# mkstepper17.net
KiCad netlist of a schematic drawn in EAGLE
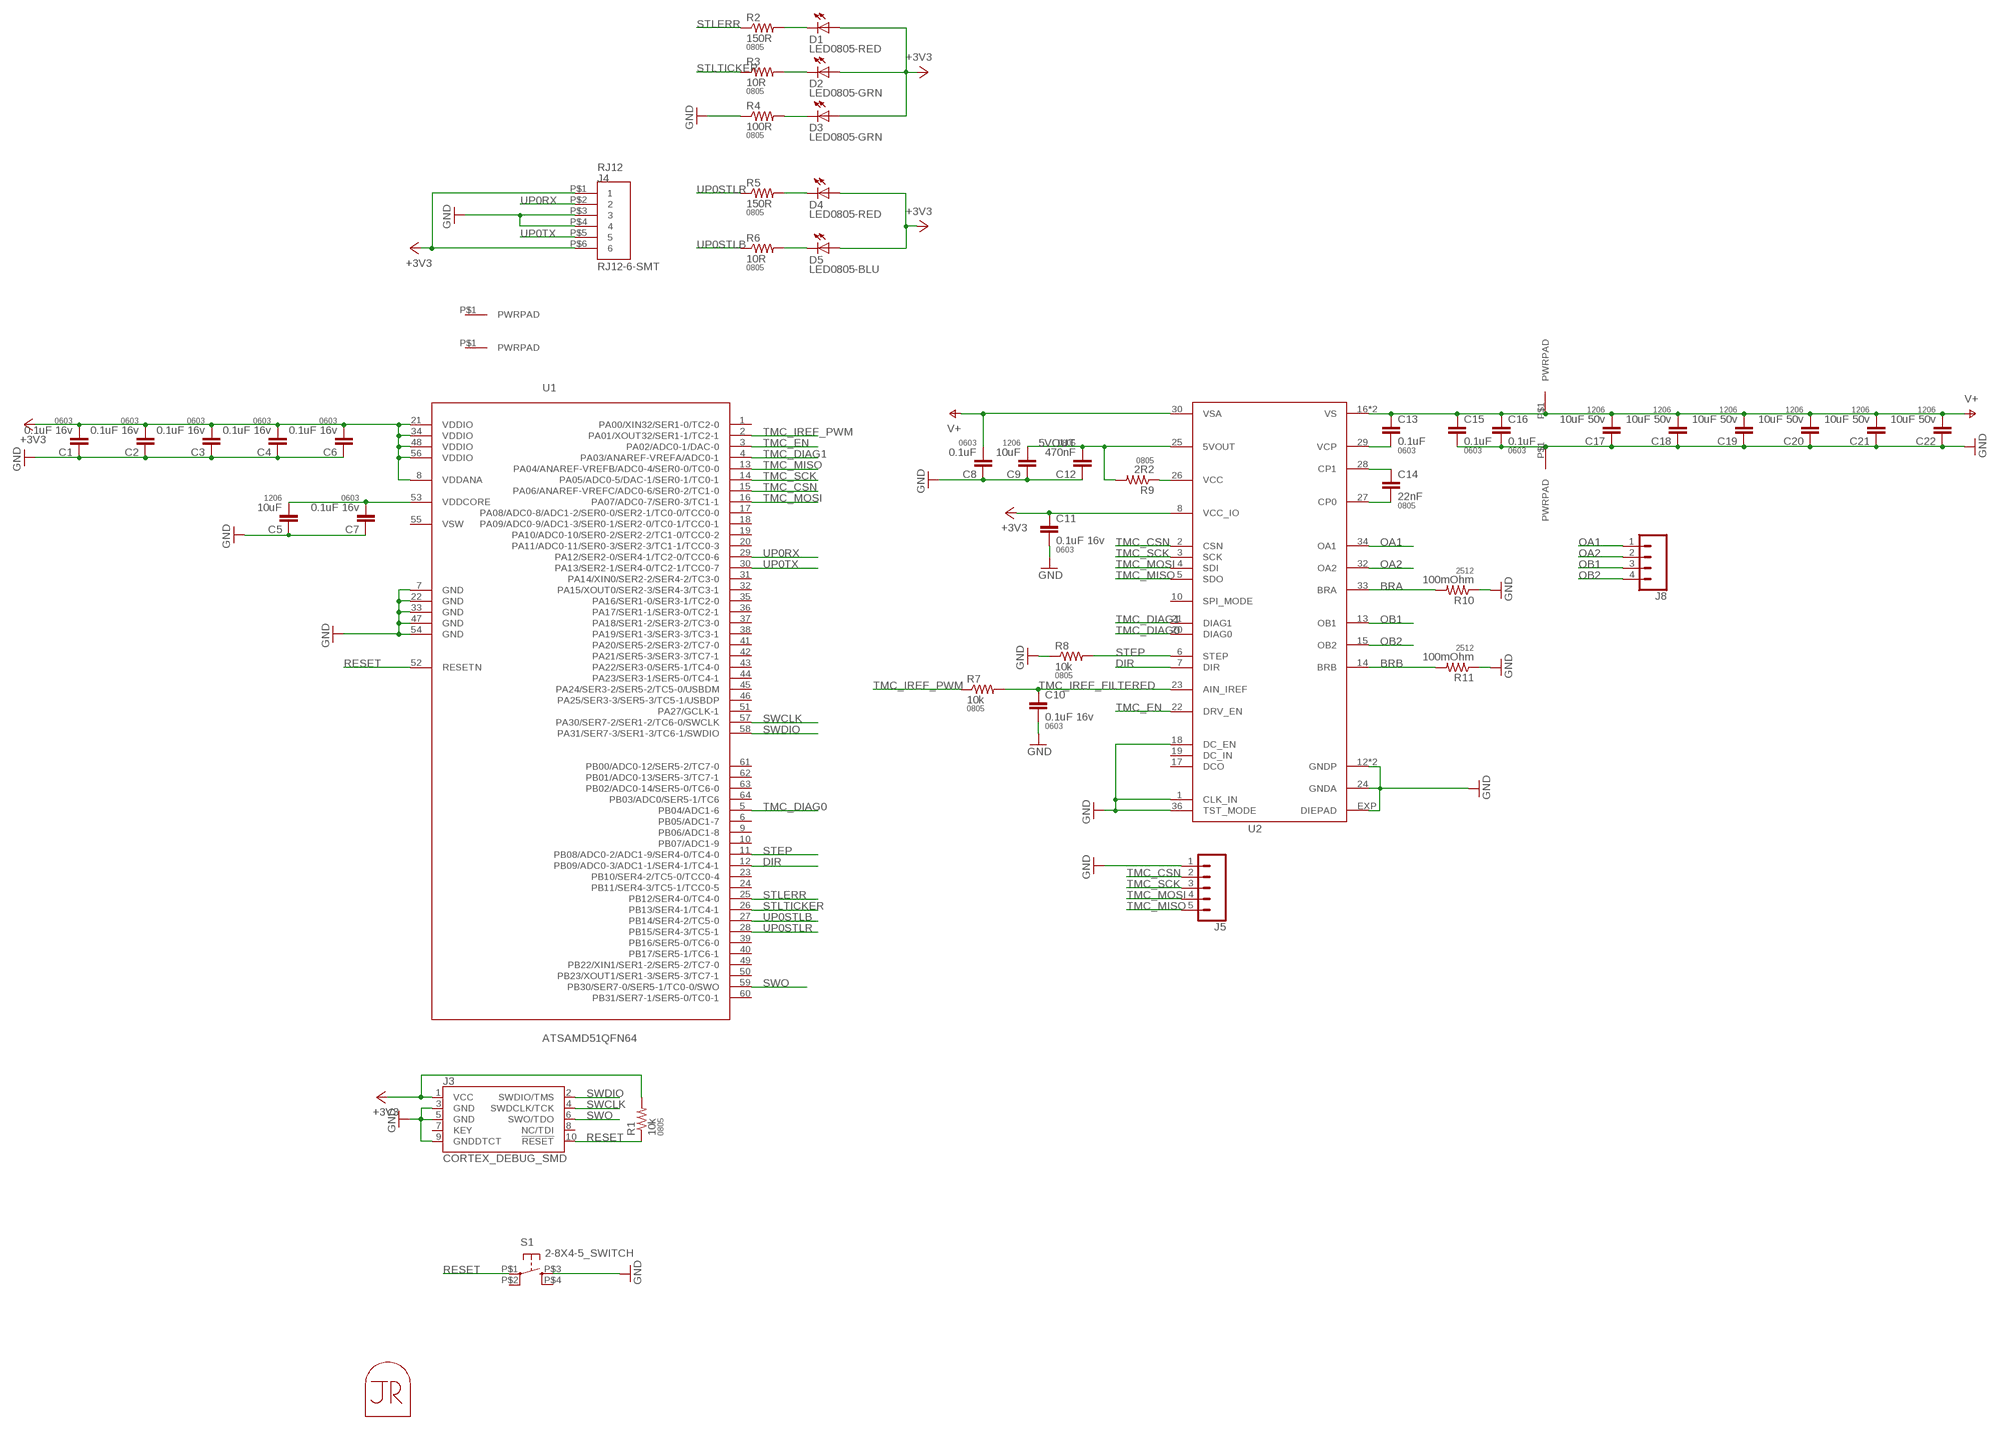
[diagram p0: schematic, sheet 1]

(export (version "E")
  (design (tool "Eeschema 10.0.6"))
  (components
    (comp (ref "C1")
      (value "0.1uF 16v")
      (footprint "eagle-import:0603-CAP")
      (libsource (lib "eagle-import") (part "CAP0603-CAP"))
    )
    (comp (ref "C2")
      (value "0.1uF 16v")
      (footprint "eagle-import:0603-CAP")
      (libsource (lib "eagle-import") (part "CAP0603-CAP"))
    )
    (comp (ref "C3")
      (value "0.1uF 16v")
      (footprint "eagle-import:0603-CAP")
      (libsource (lib "eagle-import") (part "CAP0603-CAP"))
    )
    (comp (ref "C4")
      (value "0.1uF 16v")
      (footprint "eagle-import:0603-CAP")
      (libsource (lib "eagle-import") (part "CAP0603-CAP"))
    )
    (comp (ref "C5")
      (value "10uF")
      (footprint "eagle-import:1206")
      (libsource (lib "eagle-import") (part "CAP1206"))
    )
    (comp (ref "C6")
      (value "0.1uF 16v")
      (footprint "eagle-import:0603-CAP")
      (libsource (lib "eagle-import") (part "CAP0603-CAP"))
    )
    (comp (ref "C7")
      (value "0.1uF 16v")
      (footprint "eagle-import:0603-CAP")
      (libsource (lib "eagle-import") (part "CAP0603-CAP"))
    )
    (comp (ref "C8")
      (value "0.1uF")
      (footprint "eagle-import:0603-CAP")
      (libsource (lib "eagle-import") (part "CAP0603-CAP"))
    )
    (comp (ref "C9")
      (value "10uF")
      (footprint "eagle-import:1206")
      (libsource (lib "eagle-import") (part "CAP1206"))
    )
    (comp (ref "C10")
      (value "0.1uF 16v")
      (footprint "eagle-import:0603-CAP")
      (libsource (lib "eagle-import") (part "CAP0603-CAP"))
    )
    (comp (ref "C11")
      (value "0.1uF 16v")
      (footprint "eagle-import:0603-CAP")
      (libsource (lib "eagle-import") (part "CAP0603-CAP"))
    )
    (comp (ref "C12")
      (value "470nF")
      (footprint "eagle-import:0805")
      (libsource (lib "eagle-import") (part "CAP0805"))
    )
    (comp (ref "C13")
      (value "0.1uF")
      (footprint "eagle-import:0603-CAP")
      (libsource (lib "eagle-import") (part "CAP0603-CAP"))
    )
    (comp (ref "C14")
      (value "22nF")
      (footprint "eagle-import:0805")
      (libsource (lib "eagle-import") (part "CAP0805"))
    )
    (comp (ref "C15")
      (value "0.1uF")
      (footprint "eagle-import:0603-CAP")
      (libsource (lib "eagle-import") (part "CAP0603-CAP"))
    )
    (comp (ref "C16")
      (value "0.1uF")
      (footprint "eagle-import:0603-CAP")
      (libsource (lib "eagle-import") (part "CAP0603-CAP"))
    )
    (comp (ref "C17")
      (value "10uF 50v")
      (footprint "eagle-import:1206")
      (libsource (lib "eagle-import") (part "CAP1206"))
    )
    (comp (ref "C18")
      (value "10uF 50v")
      (footprint "eagle-import:1206")
      (libsource (lib "eagle-import") (part "CAP1206"))
    )
    (comp (ref "C19")
      (value "10uF 50v")
      (footprint "eagle-import:1206")
      (libsource (lib "eagle-import") (part "CAP1206"))
    )
    (comp (ref "C20")
      (value "10uF 50v")
      (footprint "eagle-import:1206")
      (libsource (lib "eagle-import") (part "CAP1206"))
    )
    (comp (ref "C21")
      (value "10uF 50v")
      (footprint "eagle-import:1206")
      (libsource (lib "eagle-import") (part "CAP1206"))
    )
    (comp (ref "C22")
      (value "10uF 50v")
      (footprint "eagle-import:1206")
      (libsource (lib "eagle-import") (part "CAP1206"))
    )
    (comp (ref "D1")
      (value "LED0805-RED")
      (footprint "eagle-import:LED0805")
      (libsource (lib "eagle-import") (part "LED0805"))
    )
    (comp (ref "D2")
      (value "LED0805-GRN")
      (footprint "eagle-import:LED0805")
      (libsource (lib "eagle-import") (part "LED0805"))
    )
    (comp (ref "D3")
      (value "LED0805-GRN")
      (footprint "eagle-import:LED0805")
      (libsource (lib "eagle-import") (part "LED0805"))
    )
    (comp (ref "D4")
      (value "LED0805-RED")
      (footprint "eagle-import:LED0805")
      (libsource (lib "eagle-import") (part "LED0805"))
    )
    (comp (ref "D5")
      (value "LED0805-BLU")
      (footprint "eagle-import:LED0805")
      (libsource (lib "eagle-import") (part "LED0805"))
    )
    (comp (ref "J1")
      (value "PWRPADM3")
      (footprint "eagle-import:PWRPAD_3-25MM")
      (libsource (lib "eagle-import") (part "PWRPADM3"))
    )
    (comp (ref "J2")
      (value "PWRPADM3")
      (footprint "eagle-import:PWRPAD_3-25MM")
      (libsource (lib "eagle-import") (part "PWRPADM3"))
    )
    (comp (ref "J3")
      (value "CORTEX_DEBUG_SMD")
      (footprint "eagle-import:SAMTECH_FTSH-105-01")
      (libsource (lib "eagle-import") (part "CORTEX_DEBUG_SMD"))
    )
    (comp (ref "J4")
      (value "RJ12-6-SMT")
      (footprint "eagle-import:RJ12-6-SMT")
      (libsource (lib "eagle-import") (part "RJ12-6-SMT"))
    )
    (comp (ref "J5")
      (value "CONN_05NO_SILK")
      (footprint "eagle-import:1X05_NO_SILK")
      (libsource (lib "eagle-import") (part "CONN_05NO_SILK"))
    )
    (comp (ref "J6")
      (value "PWRPAD")
      (footprint "eagle-import:PWRPAD_M3-PEM-MOUNT")
      (libsource (lib "eagle-import") (part "PWRPAD"))
    )
    (comp (ref "J7")
      (value "PWRPAD")
      (footprint "eagle-import:PWRPAD_M3-PEM-MOUNT")
      (libsource (lib "eagle-import") (part "PWRPAD"))
    )
    (comp (ref "J8")
      (value "CONN_04LONGPADS")
      (footprint "eagle-import:1X04_LONGPADS")
      (libsource (lib "eagle-import") (part "CONN_04LONGPADS"))
    )
    (comp (ref "MP1")
      (value "JRTOMBSTONE")
      (footprint "eagle-import:JRTOMBSTONE")
      (libsource (lib "eagle-import") (part "JRTOMBSTONE"))
    )
    (comp (ref "R1")
      (value "10k")
      (footprint "eagle-import:0805")
      (libsource (lib "eagle-import") (part "RESISTOR0805-RES"))
    )
    (comp (ref "R2")
      (value "150R")
      (footprint "eagle-import:0805")
      (libsource (lib "eagle-import") (part "RESISTOR0805-RES"))
    )
    (comp (ref "R3")
      (value "10R")
      (footprint "eagle-import:0805")
      (libsource (lib "eagle-import") (part "RESISTOR0805-RES"))
    )
    (comp (ref "R4")
      (value "100R")
      (footprint "eagle-import:0805")
      (libsource (lib "eagle-import") (part "RESISTOR0805-RES"))
    )
    (comp (ref "R5")
      (value "150R")
      (footprint "eagle-import:0805")
      (libsource (lib "eagle-import") (part "RESISTOR0805-RES"))
    )
    (comp (ref "R6")
      (value "10R")
      (footprint "eagle-import:0805")
      (libsource (lib "eagle-import") (part "RESISTOR0805-RES"))
    )
    (comp (ref "R7")
      (value "10k")
      (footprint "eagle-import:0805")
      (libsource (lib "eagle-import") (part "RESISTOR0805-RES"))
    )
    (comp (ref "R8")
      (value "10k")
      (footprint "eagle-import:0805")
      (libsource (lib "eagle-import") (part "RESISTOR0805-RES"))
    )
    (comp (ref "R9")
      (value "2R2")
      (footprint "eagle-import:0805")
      (libsource (lib "eagle-import") (part "RESISTOR0805-RES"))
    )
    (comp (ref "R10")
      (value "100mOhm")
      (footprint "eagle-import:R2512")
      (libsource (lib "eagle-import") (part "RESISTOR2512"))
    )
    (comp (ref "R11")
      (value "100mOhm")
      (footprint "eagle-import:R2512")
      (libsource (lib "eagle-import") (part "RESISTOR2512"))
    )
    (comp (ref "S1")
      (value "2-8X4-5_SWITCH")
      (footprint "eagle-import:TACT-SWITCH-KMR6")
      (libsource (lib "eagle-import") (part "2-8X4-5_SWITCH"))
    )
    (comp (ref "U1")
      (value "ATSAMD51QFN64")
      (footprint "eagle-import:QFN-64-9X9MM")
      (libsource (lib "eagle-import") (part "ATSAMD51QFN64"))
    )
    (comp (ref "U2")
      (value "TMC2130")
      (footprint "eagle-import:QFN36-5X6")
      (libsource (lib "eagle-import") (part "TMC2130"))
    )
  )
  (nets
    (net (code "1") (name "+3V3") (class "Default")
      (node (ref "C1") (pin "2") (pinfunction "2_2") (pintype "passive"))
      (node (ref "C11") (pin "1") (pinfunction "1_1") (pintype "passive"))
      (node (ref "C2") (pin "2") (pinfunction "2_2") (pintype "passive"))
      (node (ref "C3") (pin "2") (pinfunction "2_2") (pintype "passive"))
      (node (ref "C4") (pin "2") (pinfunction "2_2") (pintype "passive"))
      (node (ref "C6") (pin "2") (pinfunction "2_2") (pintype "passive"))
      (node (ref "D1") (pin "1") (pinfunction "A_1") (pintype "passive"))
      (node (ref "D2") (pin "1") (pinfunction "A_1") (pintype "passive"))
      (node (ref "D3") (pin "1") (pinfunction "A_1") (pintype "passive"))
      (node (ref "D4") (pin "1") (pinfunction "A_1") (pintype "passive"))
      (node (ref "D5") (pin "1") (pinfunction "A_1") (pintype "passive"))
      (node (ref "J3") (pin "1") (pinfunction "VCC_1") (pintype "bidirectional"))
      (node (ref "J4") (pin "P$1") (pinfunction "1_P$1") (pintype "bidirectional"))
      (node (ref "J4") (pin "P$6") (pinfunction "6_P$6") (pintype "bidirectional"))
      (node (ref "R1") (pin "2") (pinfunction "2_2") (pintype "passive"))
      (node (ref "U1") (pin "21") (pinfunction "VDDIO_21") (pintype "bidirectional"))
      (node (ref "U1") (pin "34") (pinfunction "VDDIO_34") (pintype "bidirectional"))
      (node (ref "U1") (pin "48") (pinfunction "VDDIO_48") (pintype "bidirectional"))
      (node (ref "U1") (pin "56") (pinfunction "VDDIO_56") (pintype "bidirectional"))
      (node (ref "U1") (pin "8") (pinfunction "VDDANA_8") (pintype "bidirectional"))
      (node (ref "U2") (pin "8") (pinfunction "VCC_IO_8") (pintype "bidirectional"))
    )
    (net (code "2") (name "/5VOUT") (class "Default")
      (node (ref "C12") (pin "2") (pinfunction "2_2") (pintype "passive"))
      (node (ref "C9") (pin "2") (pinfunction "2_2") (pintype "passive"))
      (node (ref "R9") (pin "2") (pinfunction "2_2") (pintype "passive"))
      (node (ref "U2") (pin "25") (pinfunction "5VOUT_25") (pintype "bidirectional"))
    )
    (net (code "3") (name "/BRA") (class "Default")
      (node (ref "R10") (pin "2") (pinfunction "2_2") (pintype "passive"))
      (node (ref "U2") (pin "33") (pinfunction "BRA_33") (pintype "bidirectional"))
    )
    (net (code "4") (name "/BRB") (class "Default")
      (node (ref "R11") (pin "2") (pinfunction "2_2") (pintype "passive"))
      (node (ref "U2") (pin "14") (pinfunction "BRB_14") (pintype "bidirectional"))
    )
    (net (code "5") (name "/DIR") (class "Default")
      (node (ref "U1") (pin "12") (pinfunction "PB09/ADC0-3/ADC1-1/SER4-1/TC4-1_12") (pintype "bidirectional"))
      (node (ref "U2") (pin "7") (pinfunction "DIR_7") (pintype "bidirectional"))
    )
    (net (code "6") (name "/OA1") (class "Default")
      (node (ref "J8") (pin "1") (pinfunction "1_1") (pintype "passive"))
      (node (ref "U2") (pin "34") (pinfunction "OA1_34") (pintype "bidirectional"))
    )
    (net (code "7") (name "/OA2") (class "Default")
      (node (ref "J8") (pin "2") (pinfunction "2_2") (pintype "passive"))
      (node (ref "U2") (pin "32") (pinfunction "OA2_32") (pintype "bidirectional"))
    )
    (net (code "8") (name "/OB1") (class "Default")
      (node (ref "J8") (pin "3") (pinfunction "3_3") (pintype "passive"))
      (node (ref "U2") (pin "13") (pinfunction "OB1_13") (pintype "bidirectional"))
    )
    (net (code "9") (name "/OB2") (class "Default")
      (node (ref "J8") (pin "4") (pinfunction "4_4") (pintype "passive"))
      (node (ref "U2") (pin "15") (pinfunction "OB2_15") (pintype "bidirectional"))
    )
    (net (code "10") (name "/RESET") (class "Default")
      (node (ref "J3") (pin "10") (pinfunction "~{RESET}_10") (pintype "bidirectional"))
      (node (ref "R1") (pin "1") (pinfunction "1_1") (pintype "passive"))
      (node (ref "S1") (pin "P$1") (pinfunction "P_P$1") (pintype "passive"))
      (node (ref "U1") (pin "52") (pinfunction "RESETN_52") (pintype "bidirectional"))
    )
    (net (code "11") (name "/STEP") (class "Default")
      (node (ref "R8") (pin "2") (pinfunction "2_2") (pintype "passive"))
      (node (ref "U1") (pin "11") (pinfunction "PB08/ADC0-2/ADC1-9/SER4-0/TC4-0_11") (pintype "bidirectional"))
      (node (ref "U2") (pin "6") (pinfunction "STEP_6") (pintype "bidirectional"))
    )
    (net (code "12") (name "/STLERR") (class "Default")
      (node (ref "R2") (pin "1") (pinfunction "1_1") (pintype "passive"))
      (node (ref "U1") (pin "25") (pinfunction "PB12/SER4-0/TC4-0_25") (pintype "bidirectional"))
    )
    (net (code "13") (name "/STLTICKER") (class "Default")
      (node (ref "R3") (pin "1") (pinfunction "1_1") (pintype "passive"))
      (node (ref "U1") (pin "26") (pinfunction "PB13/SER4-1/TC4-1_26") (pintype "bidirectional"))
    )
    (net (code "14") (name "/SWCLK") (class "Default")
      (node (ref "J3") (pin "4") (pinfunction "SWDCLK/TCK_4") (pintype "bidirectional"))
      (node (ref "U1") (pin "57") (pinfunction "PA30/SER7-2/SER1-2/TC6-0/SWCLK_57") (pintype "bidirectional"))
    )
    (net (code "15") (name "/SWDIO") (class "Default")
      (node (ref "J3") (pin "2") (pinfunction "SWDIO/TMS_2") (pintype "bidirectional"))
      (node (ref "U1") (pin "58") (pinfunction "PA31/SER7-3/SER1-3/TC6-1/SWDIO_58") (pintype "bidirectional"))
    )
    (net (code "16") (name "/SWO") (class "Default")
      (node (ref "J3") (pin "6") (pinfunction "SWO/TDO_6") (pintype "bidirectional"))
      (node (ref "U1") (pin "59") (pinfunction "PB30/SER7-0/SER5-1/TC0-0/SWO_59") (pintype "bidirectional"))
    )
    (net (code "17") (name "/TMC_CSN") (class "Default")
      (node (ref "J5") (pin "2") (pinfunction "2_2") (pintype "passive"))
      (node (ref "U1") (pin "15") (pinfunction "PA06/ANAREF-VREFC/ADC0-6/SER0-2/TC1-0_15") (pintype "bidirectional"))
      (node (ref "U2") (pin "2") (pinfunction "CSN_2") (pintype "bidirectional"))
    )
    (net (code "18") (name "/TMC_DIAG0") (class "Default")
      (node (ref "U1") (pin "5") (pinfunction "PB04/ADC1-6_5") (pintype "bidirectional"))
      (node (ref "U2") (pin "20") (pinfunction "DIAG0_20") (pintype "bidirectional"))
    )
    (net (code "19") (name "/TMC_DIAG1") (class "Default")
      (node (ref "U1") (pin "4") (pinfunction "PA03/ANAREF-VREFA/ADC0-1_4") (pintype "bidirectional"))
      (node (ref "U2") (pin "21") (pinfunction "DIAG1_21") (pintype "bidirectional"))
    )
    (net (code "20") (name "/TMC_EN") (class "Default")
      (node (ref "U1") (pin "3") (pinfunction "PA02/ADC0-1/DAC-0_3") (pintype "bidirectional"))
      (node (ref "U2") (pin "22") (pinfunction "DRV_EN_22") (pintype "bidirectional"))
    )
    (net (code "21") (name "/TMC_IREF_FILTERED") (class "Default")
      (node (ref "C10") (pin "1") (pinfunction "1_1") (pintype "passive"))
      (node (ref "R7") (pin "2") (pinfunction "2_2") (pintype "passive"))
      (node (ref "U2") (pin "23") (pinfunction "AIN_IREF_23") (pintype "bidirectional"))
    )
    (net (code "22") (name "/TMC_IREF_PWM") (class "Default")
      (node (ref "R7") (pin "1") (pinfunction "1_1") (pintype "passive"))
      (node (ref "U1") (pin "2") (pinfunction "PA01/XOUT32/SER1-1/TC2-1_2") (pintype "bidirectional"))
    )
    (net (code "23") (name "/TMC_MISO") (class "Default")
      (node (ref "J5") (pin "5") (pinfunction "5_5") (pintype "passive"))
      (node (ref "U1") (pin "13") (pinfunction "PA04/ANAREF-VREFB/ADC0-4/SER0-0/TC0-0_13") (pintype "bidirectional"))
      (node (ref "U2") (pin "5") (pinfunction "SDO_5") (pintype "bidirectional"))
    )
    (net (code "24") (name "/TMC_MOSI") (class "Default")
      (node (ref "J5") (pin "4") (pinfunction "4_4") (pintype "passive"))
      (node (ref "U1") (pin "16") (pinfunction "PA07/ADC0-7/SER0-3/TC1-1_16") (pintype "bidirectional"))
      (node (ref "U2") (pin "4") (pinfunction "SDI_4") (pintype "bidirectional"))
    )
    (net (code "25") (name "/TMC_SCK") (class "Default")
      (node (ref "J5") (pin "3") (pinfunction "3_3") (pintype "passive"))
      (node (ref "U1") (pin "14") (pinfunction "PA05/ADC0-5/DAC-1/SER0-1/TC0-1_14") (pintype "bidirectional"))
      (node (ref "U2") (pin "3") (pinfunction "SCK_3") (pintype "bidirectional"))
    )
    (net (code "26") (name "/UP0RX") (class "Default")
      (node (ref "J4") (pin "P$2") (pinfunction "2_P$2") (pintype "bidirectional"))
      (node (ref "U1") (pin "29") (pinfunction "PA12/SER2-0/SER4-1/TC2-0/TCC0-6_29") (pintype "bidirectional"))
    )
    (net (code "27") (name "/UP0STLB") (class "Default")
      (node (ref "R6") (pin "1") (pinfunction "1_1") (pintype "passive"))
      (node (ref "U1") (pin "27") (pinfunction "PB14/SER4-2/TC5-0_27") (pintype "bidirectional"))
    )
    (net (code "28") (name "/UP0STLR") (class "Default")
      (node (ref "R5") (pin "1") (pinfunction "1_1") (pintype "passive"))
      (node (ref "U1") (pin "28") (pinfunction "PB15/SER4-3/TC5-1_28") (pintype "bidirectional"))
    )
    (net (code "29") (name "/UP0TX") (class "Default")
      (node (ref "J4") (pin "P$5") (pinfunction "5_P$5") (pintype "bidirectional"))
      (node (ref "U1") (pin "30") (pinfunction "PA13/SER2-1/SER4-0/TC2-1/TCC0-7_30") (pintype "bidirectional"))
    )
    (net (code "30") (name "GND") (class "Default")
      (node (ref "C1") (pin "1") (pinfunction "1_1") (pintype "passive"))
      (node (ref "C10") (pin "2") (pinfunction "2_2") (pintype "passive"))
      (node (ref "C11") (pin "2") (pinfunction "2_2") (pintype "passive"))
      (node (ref "C12") (pin "1") (pinfunction "1_1") (pintype "passive"))
      (node (ref "C15") (pin "2") (pinfunction "2_2") (pintype "passive"))
      (node (ref "C16") (pin "2") (pinfunction "2_2") (pintype "passive"))
      (node (ref "C17") (pin "1") (pinfunction "1_1") (pintype "passive"))
      (node (ref "C18") (pin "1") (pinfunction "1_1") (pintype "passive"))
      (node (ref "C19") (pin "1") (pinfunction "1_1") (pintype "passive"))
      (node (ref "C2") (pin "1") (pinfunction "1_1") (pintype "passive"))
      (node (ref "C20") (pin "1") (pinfunction "1_1") (pintype "passive"))
      (node (ref "C21") (pin "1") (pinfunction "1_1") (pintype "passive"))
      (node (ref "C22") (pin "1") (pinfunction "1_1") (pintype "passive"))
      (node (ref "C3") (pin "1") (pinfunction "1_1") (pintype "passive"))
      (node (ref "C4") (pin "1") (pinfunction "1_1") (pintype "passive"))
      (node (ref "C5") (pin "1") (pinfunction "1_1") (pintype "passive"))
      (node (ref "C6") (pin "1") (pinfunction "1_1") (pintype "passive"))
      (node (ref "C7") (pin "1") (pinfunction "1_1") (pintype "passive"))
      (node (ref "C8") (pin "1") (pinfunction "1_1") (pintype "passive"))
      (node (ref "C9") (pin "1") (pinfunction "1_1") (pintype "passive"))
      (node (ref "J3") (pin "3") (pinfunction "GND_3") (pintype "bidirectional"))
      (node (ref "J3") (pin "5") (pinfunction "GND_5") (pintype "bidirectional"))
      (node (ref "J3") (pin "9") (pinfunction "GNDDTCT_9") (pintype "bidirectional"))
      (node (ref "J4") (pin "P$3") (pinfunction "3_P$3") (pintype "bidirectional"))
      (node (ref "J4") (pin "P$4") (pinfunction "4_P$4") (pintype "bidirectional"))
      (node (ref "J5") (pin "1") (pinfunction "1_1") (pintype "passive"))
      (node (ref "J7") (pin "P$1") (pinfunction "PWRPAD_P$1") (pintype "bidirectional"))
      (node (ref "R10") (pin "1") (pinfunction "1_1") (pintype "passive"))
      (node (ref "R11") (pin "1") (pinfunction "1_1") (pintype "passive"))
      (node (ref "R4") (pin "1") (pinfunction "1_1") (pintype "passive"))
      (node (ref "R8") (pin "1") (pinfunction "1_1") (pintype "passive"))
      (node (ref "S1") (pin "P$3") (pinfunction "S_P$3") (pintype "passive"))
      (node (ref "U1") (pin "22") (pinfunction "GND_22") (pintype "bidirectional"))
      (node (ref "U1") (pin "33") (pinfunction "GND_33") (pintype "bidirectional"))
      (node (ref "U1") (pin "47") (pinfunction "GND_47") (pintype "bidirectional"))
      (node (ref "U1") (pin "54") (pinfunction "GND_54") (pintype "bidirectional"))
      (node (ref "U1") (pin "7") (pinfunction "GND_7") (pintype "bidirectional"))
      (node (ref "U2") (pin "1") (pinfunction "CLK_IN_1") (pintype "bidirectional"))
      (node (ref "U2") (pin "12") (pinfunction "GNDP_12") (pintype "bidirectional"))
      (node (ref "U2") (pin "18") (pinfunction "DC_EN_18") (pintype "bidirectional"))
      (node (ref "U2") (pin "24") (pinfunction "GNDA_24") (pintype "bidirectional"))
      (node (ref "U2") (pin "35") (pinfunction "GNDP_35") (pintype "bidirectional"))
      (node (ref "U2") (pin "36") (pinfunction "TST_MODE_36") (pintype "bidirectional"))
      (node (ref "U2") (pin "EXP") (pinfunction "DIEPAD_EXP") (pintype "bidirectional"))
    )
    (net (code "31") (name "Net-(D1-C)") (class "Default")
      (node (ref "D1") (pin "2") (pinfunction "C_2") (pintype "passive"))
      (node (ref "R2") (pin "2") (pinfunction "2_2") (pintype "passive"))
    )
    (net (code "32") (name "Net-(D2-C)") (class "Default")
      (node (ref "D2") (pin "2") (pinfunction "C_2") (pintype "passive"))
      (node (ref "R3") (pin "2") (pinfunction "2_2") (pintype "passive"))
    )
    (net (code "33") (name "Net-(D3-C)") (class "Default")
      (node (ref "D3") (pin "2") (pinfunction "C_2") (pintype "passive"))
      (node (ref "R4") (pin "2") (pinfunction "2_2") (pintype "passive"))
    )
    (net (code "34") (name "Net-(D4-C)") (class "Default")
      (node (ref "D4") (pin "2") (pinfunction "C_2") (pintype "passive"))
      (node (ref "R5") (pin "2") (pinfunction "2_2") (pintype "passive"))
    )
    (net (code "35") (name "Net-(D5-C)") (class "Default")
      (node (ref "D5") (pin "2") (pinfunction "C_2") (pintype "passive"))
      (node (ref "R6") (pin "2") (pinfunction "2_2") (pintype "passive"))
    )
    (net (code "36") (name "Net-(U1-VDDCORE)") (class "Default")
      (node (ref "C5") (pin "2") (pinfunction "2_2") (pintype "passive"))
      (node (ref "C7") (pin "2") (pinfunction "2_2") (pintype "passive"))
      (node (ref "U1") (pin "53") (pinfunction "VDDCORE_53") (pintype "bidirectional"))
    )
    (net (code "37") (name "Net-(U2-CP0)") (class "Default")
      (node (ref "C14") (pin "2") (pinfunction "2_2") (pintype "passive"))
      (node (ref "U2") (pin "27") (pinfunction "CP0_27") (pintype "bidirectional"))
    )
    (net (code "38") (name "Net-(U2-CP1)") (class "Default")
      (node (ref "C14") (pin "1") (pinfunction "1_1") (pintype "passive"))
      (node (ref "U2") (pin "28") (pinfunction "CP1_28") (pintype "bidirectional"))
    )
    (net (code "39") (name "Net-(U2-VCC)") (class "Default")
      (node (ref "R9") (pin "1") (pinfunction "1_1") (pintype "passive"))
      (node (ref "U2") (pin "26") (pinfunction "VCC_26") (pintype "bidirectional"))
    )
    (net (code "40") (name "Net-(U2-VCP)") (class "Default")
      (node (ref "C13") (pin "2") (pinfunction "2_2") (pintype "passive"))
      (node (ref "U2") (pin "29") (pinfunction "VCP_29") (pintype "bidirectional"))
    )
    (net (code "41") (name "V+") (class "Default")
      (node (ref "C13") (pin "1") (pinfunction "1_1") (pintype "passive"))
      (node (ref "C15") (pin "1") (pinfunction "1_1") (pintype "passive"))
      (node (ref "C16") (pin "1") (pinfunction "1_1") (pintype "passive"))
      (node (ref "C17") (pin "2") (pinfunction "2_2") (pintype "passive"))
      (node (ref "C18") (pin "2") (pinfunction "2_2") (pintype "passive"))
      (node (ref "C19") (pin "2") (pinfunction "2_2") (pintype "passive"))
      (node (ref "C20") (pin "2") (pinfunction "2_2") (pintype "passive"))
      (node (ref "C21") (pin "2") (pinfunction "2_2") (pintype "passive"))
      (node (ref "C22") (pin "2") (pinfunction "2_2") (pintype "passive"))
      (node (ref "C8") (pin "2") (pinfunction "2_2") (pintype "passive"))
      (node (ref "J6") (pin "P$1") (pinfunction "PWRPAD_P$1") (pintype "bidirectional"))
      (node (ref "U2") (pin "16") (pinfunction "VS_16") (pintype "bidirectional"))
      (node (ref "U2") (pin "30") (pinfunction "VSA_30") (pintype "bidirectional"))
      (node (ref "U2") (pin "31") (pinfunction "VS_31") (pintype "bidirectional"))
    )
    (net (code "42") (name "unconnected-(J1-PWRPAD-PadP$1)") (class "Default")
      (node (ref "J1") (pin "P$1") (pinfunction "PWRPAD_P$1") (pintype "bidirectional"))
    )
    (net (code "43") (name "unconnected-(J2-PWRPAD-PadP$1)") (class "Default")
      (node (ref "J2") (pin "P$1") (pinfunction "PWRPAD_P$1") (pintype "bidirectional"))
    )
    (net (code "44") (name "unconnected-(J3-KEY-Pad7)") (class "Default")
      (node (ref "J3") (pin "7") (pinfunction "KEY_7") (pintype "bidirectional"))
    )
    (net (code "45") (name "unconnected-(J3-NC{slash}TDI-Pad8)") (class "Default")
      (node (ref "J3") (pin "8") (pinfunction "NC/TDI_8") (pintype "bidirectional"))
    )
    (net (code "46") (name "unconnected-(S1-P1-PadP$2)") (class "Default")
      (node (ref "S1") (pin "P$2") (pinfunction "P1_P$2") (pintype "passive"))
    )
    (net (code "47") (name "unconnected-(S1-S1-PadP$4)") (class "Default")
      (node (ref "S1") (pin "P$4") (pinfunction "S1_P$4") (pintype "passive"))
    )
    (net (code "48") (name "unconnected-(U1-PA00{slash}XIN32{slash}SER1-0{slash}TC2-0-Pad1)") (class "Default")
      (node (ref "U1") (pin "1") (pinfunction "PA00/XIN32/SER1-0/TC2-0_1") (pintype "bidirectional"))
    )
    (net (code "49") (name "unconnected-(U1-PA08{slash}ADC0-8{slash}ADC1-2{slash}SER0-0{slash}SER2-1{slash}TC0-0{slash}TCC0-0-Pad17)") (class "Default")
      (node (ref "U1") (pin "17") (pinfunction "PA08/ADC0-8/ADC1-2/SER0-0/SER2-1/TC0-0/TCC0-0_17") (pintype "bidirectional"))
    )
    (net (code "50") (name "unconnected-(U1-PA09{slash}ADC0-9{slash}ADC1-3{slash}SER0-1{slash}SER2-0{slash}TC0-1{slash}TCC0-1-Pad18)") (class "Default")
      (node (ref "U1") (pin "18") (pinfunction "PA09/ADC0-9/ADC1-3/SER0-1/SER2-0/TC0-1/TCC0-1_18") (pintype "bidirectional"))
    )
    (net (code "51") (name "unconnected-(U1-PA10{slash}ADC0-10{slash}SER0-2{slash}SER2-2{slash}TC1-0{slash}TCC0-2-Pad19)") (class "Default")
      (node (ref "U1") (pin "19") (pinfunction "PA10/ADC0-10/SER0-2/SER2-2/TC1-0/TCC0-2_19") (pintype "bidirectional"))
    )
    (net (code "52") (name "unconnected-(U1-PA11{slash}ADC0-11{slash}SER0-3{slash}SER2-3{slash}TC1-1{slash}TCC0-3-Pad20)") (class "Default")
      (node (ref "U1") (pin "20") (pinfunction "PA11/ADC0-11/SER0-3/SER2-3/TC1-1/TCC0-3_20") (pintype "bidirectional"))
    )
    (net (code "53") (name "unconnected-(U1-PA14{slash}XIN0{slash}SER2-2{slash}SER4-2{slash}TC3-0-Pad31)") (class "Default")
      (node (ref "U1") (pin "31") (pinfunction "PA14/XIN0/SER2-2/SER4-2/TC3-0_31") (pintype "bidirectional"))
    )
    (net (code "54") (name "unconnected-(U1-PA15{slash}XOUT0{slash}SER2-3{slash}SER4-3{slash}TC3-1-Pad32)") (class "Default")
      (node (ref "U1") (pin "32") (pinfunction "PA15/XOUT0/SER2-3/SER4-3/TC3-1_32") (pintype "bidirectional"))
    )
    (net (code "55") (name "unconnected-(U1-PA16{slash}SER1-0{slash}SER3-1{slash}TC2-0-Pad35)") (class "Default")
      (node (ref "U1") (pin "35") (pinfunction "PA16/SER1-0/SER3-1/TC2-0_35") (pintype "bidirectional"))
    )
    (net (code "56") (name "unconnected-(U1-PA17{slash}SER1-1{slash}SER3-0{slash}TC2-1-Pad36)") (class "Default")
      (node (ref "U1") (pin "36") (pinfunction "PA17/SER1-1/SER3-0/TC2-1_36") (pintype "bidirectional"))
    )
    (net (code "57") (name "unconnected-(U1-PA18{slash}SER1-2{slash}SER3-2{slash}TC3-0-Pad37)") (class "Default")
      (node (ref "U1") (pin "37") (pinfunction "PA18/SER1-2/SER3-2/TC3-0_37") (pintype "bidirectional"))
    )
    (net (code "58") (name "unconnected-(U1-PA19{slash}SER1-3{slash}SER3-3{slash}TC3-1-Pad38)") (class "Default")
      (node (ref "U1") (pin "38") (pinfunction "PA19/SER1-3/SER3-3/TC3-1_38") (pintype "bidirectional"))
    )
    (net (code "59") (name "unconnected-(U1-PA20{slash}SER5-2{slash}SER3-2{slash}TC7-0-Pad41)") (class "Default")
      (node (ref "U1") (pin "41") (pinfunction "PA20/SER5-2/SER3-2/TC7-0_41") (pintype "bidirectional"))
    )
    (net (code "60") (name "unconnected-(U1-PA21{slash}SER5-3{slash}SER3-3{slash}TC7-1-Pad42)") (class "Default")
      (node (ref "U1") (pin "42") (pinfunction "PA21/SER5-3/SER3-3/TC7-1_42") (pintype "bidirectional"))
    )
    (net (code "61") (name "unconnected-(U1-PA22{slash}SER3-0{slash}SER5-1{slash}TC4-0-Pad43)") (class "Default")
      (node (ref "U1") (pin "43") (pinfunction "PA22/SER3-0/SER5-1/TC4-0_43") (pintype "bidirectional"))
    )
    (net (code "62") (name "unconnected-(U1-PA23{slash}SER3-1{slash}SER5-0{slash}TC4-1-Pad44)") (class "Default")
      (node (ref "U1") (pin "44") (pinfunction "PA23/SER3-1/SER5-0/TC4-1_44") (pintype "bidirectional"))
    )
    (net (code "63") (name "unconnected-(U1-PA24{slash}SER3-2{slash}SER5-2{slash}TC5-0{slash}USBDM-Pad45)") (class "Default")
      (node (ref "U1") (pin "45") (pinfunction "PA24/SER3-2/SER5-2/TC5-0/USBDM_45") (pintype "bidirectional"))
    )
    (net (code "64") (name "unconnected-(U1-PA25{slash}SER3-3{slash}SER5-3{slash}TC5-1{slash}USBDP-Pad46)") (class "Default")
      (node (ref "U1") (pin "46") (pinfunction "PA25/SER3-3/SER5-3/TC5-1/USBDP_46") (pintype "bidirectional"))
    )
    (net (code "65") (name "unconnected-(U1-PA27{slash}GCLK-1-Pad51)") (class "Default")
      (node (ref "U1") (pin "51") (pinfunction "PA27/GCLK-1_51") (pintype "bidirectional"))
    )
    (net (code "66") (name "unconnected-(U1-PB00{slash}ADC0-12{slash}SER5-2{slash}TC7-0-Pad61)") (class "Default")
      (node (ref "U1") (pin "61") (pinfunction "PB00/ADC0-12/SER5-2/TC7-0_61") (pintype "bidirectional"))
    )
    (net (code "67") (name "unconnected-(U1-PB01{slash}ADC0-13{slash}SER5-3{slash}TC7-1-Pad62)") (class "Default")
      (node (ref "U1") (pin "62") (pinfunction "PB01/ADC0-13/SER5-3/TC7-1_62") (pintype "bidirectional"))
    )
    (net (code "68") (name "unconnected-(U1-PB02{slash}ADC0-14{slash}SER5-0{slash}TC6-0-Pad63)") (class "Default")
      (node (ref "U1") (pin "63") (pinfunction "PB02/ADC0-14/SER5-0/TC6-0_63") (pintype "bidirectional"))
    )
    (net (code "69") (name "unconnected-(U1-PB03{slash}ADC0{slash}SER5-1{slash}TC6-Pad64)") (class "Default")
      (node (ref "U1") (pin "64") (pinfunction "PB03/ADC0/SER5-1/TC6_64") (pintype "bidirectional"))
    )
    (net (code "70") (name "unconnected-(U1-PB05{slash}ADC1-7-Pad6)") (class "Default")
      (node (ref "U1") (pin "6") (pinfunction "PB05/ADC1-7_6") (pintype "bidirectional"))
    )
    (net (code "71") (name "unconnected-(U1-PB06{slash}ADC1-8-Pad9)") (class "Default")
      (node (ref "U1") (pin "9") (pinfunction "PB06/ADC1-8_9") (pintype "bidirectional"))
    )
    (net (code "72") (name "unconnected-(U1-PB07{slash}ADC1-9-Pad10)") (class "Default")
      (node (ref "U1") (pin "10") (pinfunction "PB07/ADC1-9_10") (pintype "bidirectional"))
    )
    (net (code "73") (name "unconnected-(U1-PB10{slash}SER4-2{slash}TC5-0{slash}TCC0-4-Pad23)") (class "Default")
      (node (ref "U1") (pin "23") (pinfunction "PB10/SER4-2/TC5-0/TCC0-4_23") (pintype "bidirectional"))
    )
    (net (code "74") (name "unconnected-(U1-PB11{slash}SER4-3{slash}TC5-1{slash}TCC0-5-Pad24)") (class "Default")
      (node (ref "U1") (pin "24") (pinfunction "PB11/SER4-3/TC5-1/TCC0-5_24") (pintype "bidirectional"))
    )
    (net (code "75") (name "unconnected-(U1-PB16{slash}SER5-0{slash}TC6-0-Pad39)") (class "Default")
      (node (ref "U1") (pin "39") (pinfunction "PB16/SER5-0/TC6-0_39") (pintype "bidirectional"))
    )
    (net (code "76") (name "unconnected-(U1-PB17{slash}SER5-1{slash}TC6-1-Pad40)") (class "Default")
      (node (ref "U1") (pin "40") (pinfunction "PB17/SER5-1/TC6-1_40") (pintype "bidirectional"))
    )
    (net (code "77") (name "unconnected-(U1-PB22{slash}XIN1{slash}SER1-2{slash}SER5-2{slash}TC7-0-Pad49)") (class "Default")
      (node (ref "U1") (pin "49") (pinfunction "PB22/XIN1/SER1-2/SER5-2/TC7-0_49") (pintype "bidirectional"))
    )
    (net (code "78") (name "unconnected-(U1-PB23{slash}XOUT1{slash}SER1-3{slash}SER5-3{slash}TC7-1-Pad50)") (class "Default")
      (node (ref "U1") (pin "50") (pinfunction "PB23/XOUT1/SER1-3/SER5-3/TC7-1_50") (pintype "bidirectional"))
    )
    (net (code "79") (name "unconnected-(U1-PB31{slash}SER7-1{slash}SER5-0{slash}TC0-1-Pad60)") (class "Default")
      (node (ref "U1") (pin "60") (pinfunction "PB31/SER7-1/SER5-0/TC0-1_60") (pintype "bidirectional"))
    )
    (net (code "80") (name "unconnected-(U1-VSW-Pad55)") (class "Default")
      (node (ref "U1") (pin "55") (pinfunction "VSW_55") (pintype "bidirectional"))
    )
    (net (code "81") (name "unconnected-(U2-DCO-Pad17)") (class "Default")
      (node (ref "U2") (pin "17") (pinfunction "DCO_17") (pintype "bidirectional"))
    )
    (net (code "82") (name "unconnected-(U2-DC_IN-Pad19)") (class "Default")
      (node (ref "U2") (pin "19") (pinfunction "DC_IN_19") (pintype "bidirectional"))
    )
    (net (code "83") (name "unconnected-(U2-SPI_MODE-Pad10)") (class "Default")
      (node (ref "U2") (pin "10") (pinfunction "SPI_MODE_10") (pintype "bidirectional"))
    )
  )
)
